# a-star-is31.net
KiCad netlist of a schematic drawn in EAGLE
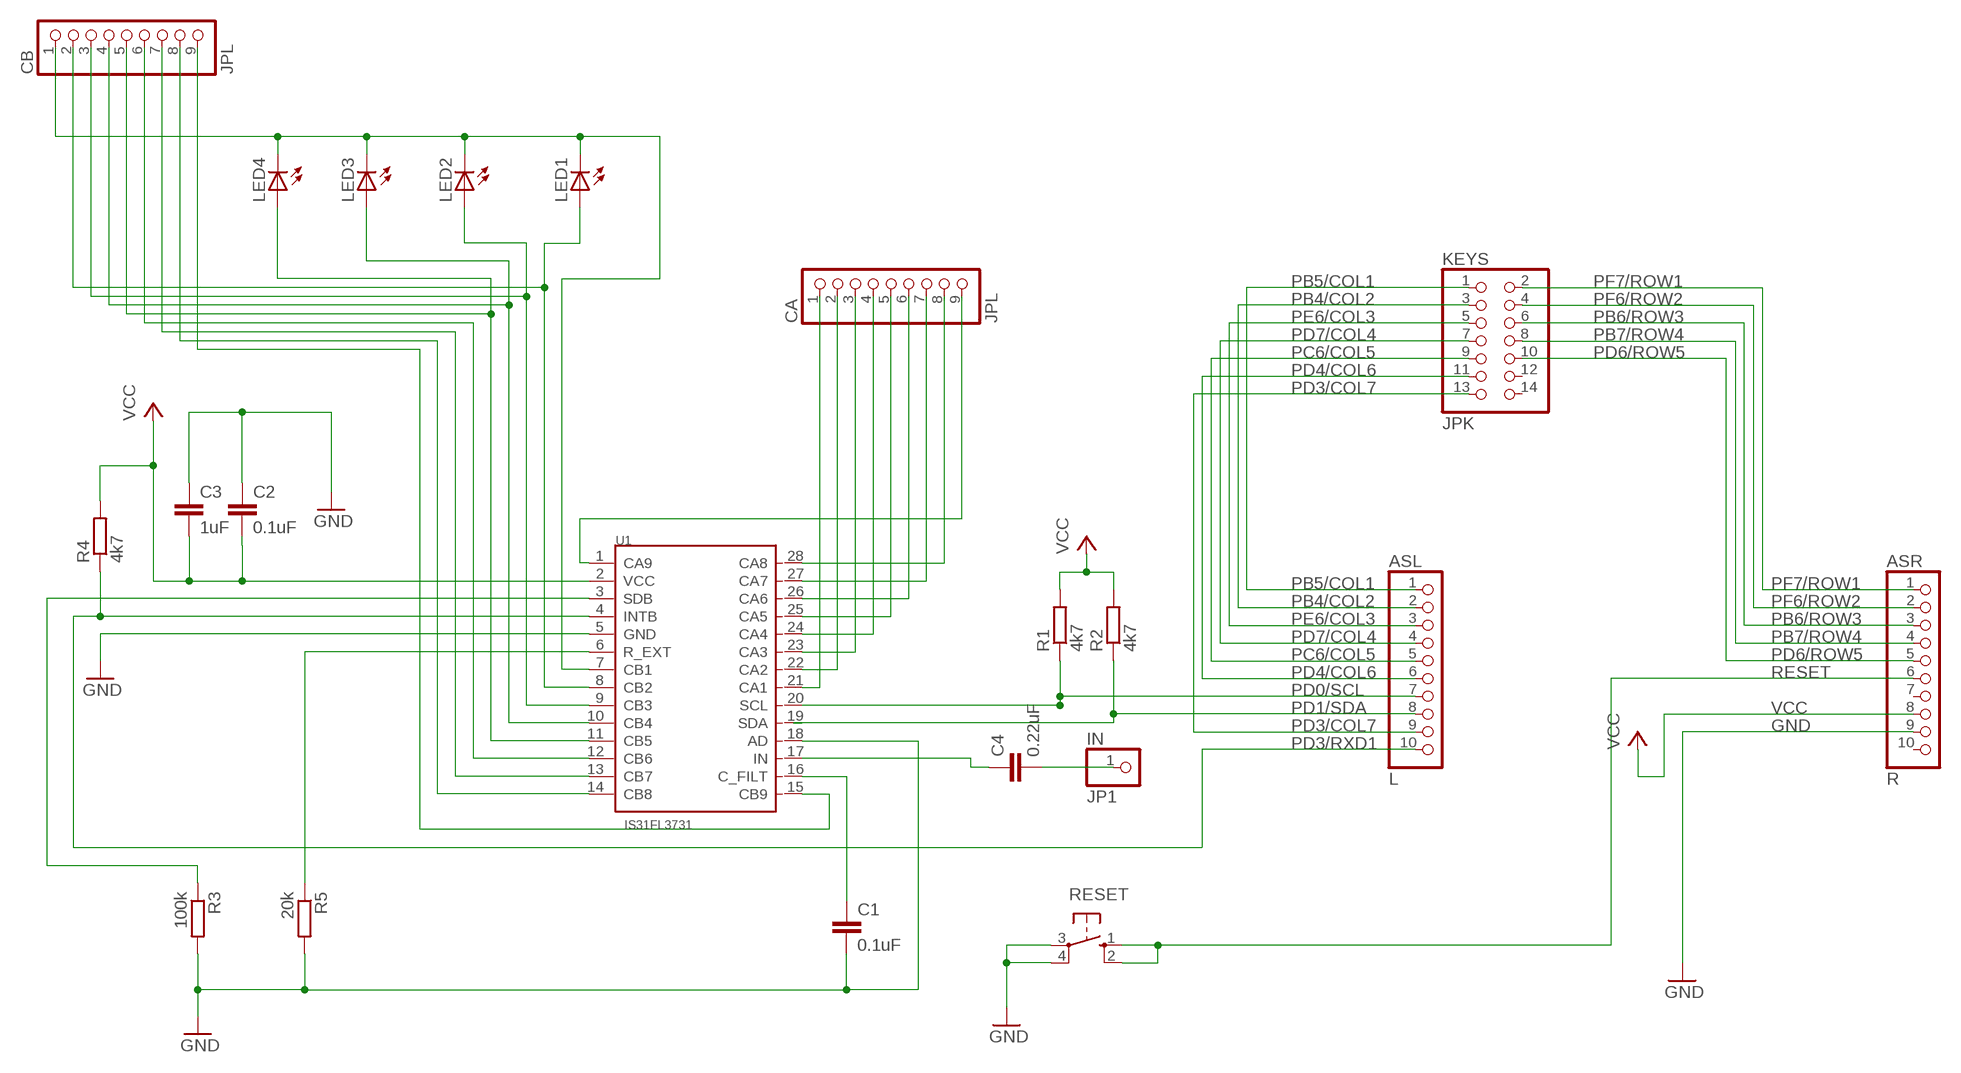
[diagram p0: schematic, sheet 1]

(export (version "E")
  (design (tool "Eeschema 10.0.6"))
  (components
    (comp (ref "ASL")
      (value "L")
      (footprint "eagle-import:1X10")
      (libsource (lib "eagle-import") (part "PINHD-1X10"))
    )
    (comp (ref "ASR")
      (value "R")
      (footprint "eagle-import:1X10")
      (libsource (lib "eagle-import") (part "PINHD-1X10"))
    )
    (comp (ref "C1")
      (value "0.1uF")
      (footprint "eagle-import:C025-025X050")
      (libsource (lib "eagle-import") (part "C-EU025-025X050"))
    )
    (comp (ref "C2")
      (value "0.1uF")
      (footprint "eagle-import:C025-025X050")
      (libsource (lib "eagle-import") (part "C-EU025-025X050"))
    )
    (comp (ref "C3")
      (value "1uF")
      (footprint "eagle-import:C025-025X050")
      (libsource (lib "eagle-import") (part "C-EU025-025X050"))
    )
    (comp (ref "C4")
      (value "0.22uF")
      (footprint "eagle-import:C025-025X050")
      (libsource (lib "eagle-import") (part "C-EU025-025X050"))
    )
    (comp (ref "CA")
      (value "JPL")
      (footprint "eagle-import:1X09")
      (libsource (lib "eagle-import") (part "PINHD-1X9"))
    )
    (comp (ref "CB")
      (value "JPL")
      (footprint "eagle-import:1X09")
      (libsource (lib "eagle-import") (part "PINHD-1X9"))
    )
    (comp (ref "IN")
      (value "JP1")
      (footprint "eagle-import:1X01")
      (libsource (lib "eagle-import") (part "PINHD-1X1"))
    )
    (comp (ref "KEYS")
      (value "JPK")
      (footprint "eagle-import:2X07")
      (libsource (lib "eagle-import") (part "PINHD-2X7"))
    )
    (comp (ref "LED1")
      (value "LED3MM")
      (footprint "eagle-import:LED3MM")
      (libsource (lib "eagle-import") (part "LED3MM"))
    )
    (comp (ref "LED2")
      (value "LED3MM")
      (footprint "eagle-import:LED3MM")
      (libsource (lib "eagle-import") (part "LED3MM"))
    )
    (comp (ref "LED3")
      (value "LED3MM")
      (footprint "eagle-import:LED3MM")
      (libsource (lib "eagle-import") (part "LED3MM"))
    )
    (comp (ref "LED4")
      (value "LED3MM")
      (footprint "eagle-import:LED3MM")
      (libsource (lib "eagle-import") (part "LED3MM"))
    )
    (comp (ref "R1")
      (value "4k7")
      (footprint "eagle-import:0207_10")
      (libsource (lib "eagle-import") (part "R-EU_0207/10"))
    )
    (comp (ref "R2")
      (value "4k7")
      (footprint "eagle-import:0207_10")
      (libsource (lib "eagle-import") (part "R-EU_0207/10"))
    )
    (comp (ref "R3")
      (value "100k")
      (footprint "eagle-import:0207_10")
      (libsource (lib "eagle-import") (part "R-EU_0207/10"))
    )
    (comp (ref "R4")
      (value "4k7")
      (footprint "eagle-import:0207_10")
      (libsource (lib "eagle-import") (part "R-EU_0207/10"))
    )
    (comp (ref "R5")
      (value "20k")
      (footprint "eagle-import:0207_10")
      (libsource (lib "eagle-import") (part "R-EU_0207/10"))
    )
    (comp (ref "RESET")
      (value "10-XX")
      (footprint "eagle-import:B3F-10XX")
      (fields (field (name "MPN") "B3F-1000"))
      (libsource (lib "eagle-import") (part "10-XX"))
    )
    (comp (ref "U1")
      (value "IS31FL3731")
      (footprint "eagle-import:SSOP28-0.65-10.2X5.2MM")
      (fields (field (name "MPN") "WM8731SEDS/V"))
      (libsource (lib "eagle-import") (part "IS31FL3731(SSOP28)"))
    )
  )
  (nets
    (net (code "1") (name "/PB4{slash}COL2") (class "Default")
      (node (ref "ASL") (pin "2") (pinfunction "2_2") (pintype "passive"))
      (node (ref "KEYS") (pin "3") (pinfunction "3_3") (pintype "passive"))
    )
    (net (code "2") (name "/PB5{slash}COL1") (class "Default")
      (node (ref "ASL") (pin "1") (pinfunction "1_1") (pintype "passive"))
      (node (ref "KEYS") (pin "1") (pinfunction "1_1") (pintype "passive"))
    )
    (net (code "3") (name "/PB6{slash}ROW3") (class "Default")
      (node (ref "ASR") (pin "3") (pinfunction "3_3") (pintype "passive"))
      (node (ref "KEYS") (pin "6") (pinfunction "6_6") (pintype "passive"))
    )
    (net (code "4") (name "/PB7{slash}ROW4") (class "Default")
      (node (ref "ASR") (pin "4") (pinfunction "4_4") (pintype "passive"))
      (node (ref "KEYS") (pin "8") (pinfunction "8_8") (pintype "passive"))
    )
    (net (code "5") (name "/PC6{slash}COL5") (class "Default")
      (node (ref "ASL") (pin "5") (pinfunction "5_5") (pintype "passive"))
      (node (ref "KEYS") (pin "9") (pinfunction "9_9") (pintype "passive"))
    )
    (net (code "6") (name "/PD0{slash}SCL") (class "Default")
      (node (ref "ASL") (pin "7") (pinfunction "7_7") (pintype "passive"))
      (node (ref "R1") (pin "1") (pinfunction "1_1") (pintype "passive"))
      (node (ref "U1") (pin "20") (pinfunction "SCL_20") (pintype "bidirectional"))
    )
    (net (code "7") (name "/PD1{slash}SDA") (class "Default")
      (node (ref "ASL") (pin "8") (pinfunction "8_8") (pintype "passive"))
      (node (ref "R2") (pin "1") (pinfunction "1_1") (pintype "passive"))
      (node (ref "U1") (pin "19") (pinfunction "SDA_19") (pintype "bidirectional"))
    )
    (net (code "8") (name "/PD3{slash}COL7") (class "Default")
      (node (ref "ASL") (pin "9") (pinfunction "9_9") (pintype "passive"))
      (node (ref "KEYS") (pin "13") (pinfunction "13_13") (pintype "passive"))
    )
    (net (code "9") (name "/PD3{slash}RXD1") (class "Default")
      (node (ref "ASL") (pin "10") (pinfunction "10_10") (pintype "passive"))
      (node (ref "R4") (pin "1") (pinfunction "1_1") (pintype "passive"))
      (node (ref "U1") (pin "4") (pinfunction "INTB_4") (pintype "bidirectional"))
    )
    (net (code "10") (name "/PD4{slash}COL6") (class "Default")
      (node (ref "ASL") (pin "6") (pinfunction "6_6") (pintype "passive"))
      (node (ref "KEYS") (pin "11") (pinfunction "11_11") (pintype "passive"))
    )
    (net (code "11") (name "/PD6{slash}ROW5") (class "Default")
      (node (ref "ASR") (pin "5") (pinfunction "5_5") (pintype "passive"))
      (node (ref "KEYS") (pin "10") (pinfunction "10_10") (pintype "passive"))
    )
    (net (code "12") (name "/PD7{slash}COL4") (class "Default")
      (node (ref "ASL") (pin "4") (pinfunction "4_4") (pintype "passive"))
      (node (ref "KEYS") (pin "7") (pinfunction "7_7") (pintype "passive"))
    )
    (net (code "13") (name "/PE6{slash}COL3") (class "Default")
      (node (ref "ASL") (pin "3") (pinfunction "3_3") (pintype "passive"))
      (node (ref "KEYS") (pin "5") (pinfunction "5_5") (pintype "passive"))
    )
    (net (code "14") (name "/PF6{slash}ROW2") (class "Default")
      (node (ref "ASR") (pin "2") (pinfunction "2_2") (pintype "passive"))
      (node (ref "KEYS") (pin "4") (pinfunction "4_4") (pintype "passive"))
    )
    (net (code "15") (name "/PF7{slash}ROW1") (class "Default")
      (node (ref "ASR") (pin "1") (pinfunction "1_1") (pintype "passive"))
      (node (ref "KEYS") (pin "2") (pinfunction "2_2") (pintype "passive"))
    )
    (net (code "16") (name "/RESET") (class "Default")
      (node (ref "ASR") (pin "6") (pinfunction "6_6") (pintype "passive"))
      (node (ref "RESET") (pin "1") (pinfunction "S_1") (pintype "passive"))
      (node (ref "RESET") (pin "2") (pinfunction "S1_2") (pintype "passive"))
    )
    (net (code "17") (name "GND") (class "Default")
      (node (ref "ASR") (pin "9") (pinfunction "9_9") (pintype "passive"))
      (node (ref "C1") (pin "2") (pinfunction "2_2") (pintype "passive"))
      (node (ref "C2") (pin "1") (pinfunction "1_1") (pintype "passive"))
      (node (ref "C3") (pin "1") (pinfunction "1_1") (pintype "passive"))
      (node (ref "R3") (pin "2") (pinfunction "2_2") (pintype "passive"))
      (node (ref "R5") (pin "2") (pinfunction "2_2") (pintype "passive"))
      (node (ref "RESET") (pin "3") (pinfunction "P_3") (pintype "passive"))
      (node (ref "RESET") (pin "4") (pinfunction "P1_4") (pintype "passive"))
      (node (ref "U1") (pin "18") (pinfunction "AD_18") (pintype "bidirectional"))
      (node (ref "U1") (pin "5") (pinfunction "GND_5") (pintype "bidirectional"))
    )
    (net (code "18") (name "Net-(C4-Pad2)") (class "Default")
      (node (ref "C4") (pin "2") (pinfunction "2_2") (pintype "passive"))
      (node (ref "IN") (pin "1") (pinfunction "1_1") (pintype "passive"))
    )
    (net (code "19") (name "Net-(LED1-C)") (class "Default")
      (node (ref "CB") (pin "1") (pinfunction "1_1") (pintype "passive"))
      (node (ref "LED1") (pin "K") (pinfunction "C_K") (pintype "passive"))
      (node (ref "LED2") (pin "K") (pinfunction "C_K") (pintype "passive"))
      (node (ref "LED3") (pin "K") (pinfunction "C_K") (pintype "passive"))
      (node (ref "LED4") (pin "K") (pinfunction "C_K") (pintype "passive"))
      (node (ref "U1") (pin "7") (pinfunction "CB1_7") (pintype "bidirectional"))
    )
    (net (code "20") (name "Net-(U1-CA1)") (class "Default")
      (node (ref "CA") (pin "1") (pinfunction "1_1") (pintype "passive"))
      (node (ref "U1") (pin "21") (pinfunction "CA1_21") (pintype "bidirectional"))
    )
    (net (code "21") (name "Net-(U1-CA2)") (class "Default")
      (node (ref "CA") (pin "2") (pinfunction "2_2") (pintype "passive"))
      (node (ref "U1") (pin "22") (pinfunction "CA2_22") (pintype "bidirectional"))
    )
    (net (code "22") (name "Net-(U1-CA3)") (class "Default")
      (node (ref "CA") (pin "3") (pinfunction "3_3") (pintype "passive"))
      (node (ref "U1") (pin "23") (pinfunction "CA3_23") (pintype "bidirectional"))
    )
    (net (code "23") (name "Net-(U1-CA4)") (class "Default")
      (node (ref "CA") (pin "4") (pinfunction "4_4") (pintype "passive"))
      (node (ref "U1") (pin "24") (pinfunction "CA4_24") (pintype "bidirectional"))
    )
    (net (code "24") (name "Net-(U1-CA5)") (class "Default")
      (node (ref "CA") (pin "5") (pinfunction "5_5") (pintype "passive"))
      (node (ref "U1") (pin "25") (pinfunction "CA5_25") (pintype "bidirectional"))
    )
    (net (code "25") (name "Net-(U1-CA6)") (class "Default")
      (node (ref "CA") (pin "6") (pinfunction "6_6") (pintype "passive"))
      (node (ref "U1") (pin "26") (pinfunction "CA6_26") (pintype "bidirectional"))
    )
    (net (code "26") (name "Net-(U1-CA7)") (class "Default")
      (node (ref "CA") (pin "7") (pinfunction "7_7") (pintype "passive"))
      (node (ref "U1") (pin "27") (pinfunction "CA7_27") (pintype "power_in"))
    )
    (net (code "27") (name "Net-(U1-CA8)") (class "Default")
      (node (ref "CA") (pin "8") (pinfunction "8_8") (pintype "passive"))
      (node (ref "U1") (pin "28") (pinfunction "CA8_28") (pintype "power_in"))
    )
    (net (code "28") (name "Net-(U1-CA9)") (class "Default")
      (node (ref "CA") (pin "9") (pinfunction "9_9") (pintype "passive"))
      (node (ref "U1") (pin "1") (pinfunction "CA9_1") (pintype "power_in"))
    )
    (net (code "29") (name "Net-(U1-CB2)") (class "Default")
      (node (ref "CB") (pin "2") (pinfunction "2_2") (pintype "passive"))
      (node (ref "LED1") (pin "A") (pinfunction "A_A") (pintype "passive"))
      (node (ref "U1") (pin "8") (pinfunction "CB2_8") (pintype "power_in"))
    )
    (net (code "30") (name "Net-(U1-CB3)") (class "Default")
      (node (ref "CB") (pin "3") (pinfunction "3_3") (pintype "passive"))
      (node (ref "LED2") (pin "A") (pinfunction "A_A") (pintype "passive"))
      (node (ref "U1") (pin "9") (pinfunction "CB3_9") (pintype "bidirectional"))
    )
    (net (code "31") (name "Net-(U1-CB4)") (class "Default")
      (node (ref "CB") (pin "4") (pinfunction "4_4") (pintype "passive"))
      (node (ref "LED3") (pin "A") (pinfunction "A_A") (pintype "passive"))
      (node (ref "U1") (pin "10") (pinfunction "CB4_10") (pintype "bidirectional"))
    )
    (net (code "32") (name "Net-(U1-CB5)") (class "Default")
      (node (ref "CB") (pin "5") (pinfunction "5_5") (pintype "passive"))
      (node (ref "LED4") (pin "A") (pinfunction "A_A") (pintype "passive"))
      (node (ref "U1") (pin "11") (pinfunction "CB5_11") (pintype "bidirectional"))
    )
    (net (code "33") (name "Net-(U1-CB6)") (class "Default")
      (node (ref "CB") (pin "6") (pinfunction "6_6") (pintype "passive"))
      (node (ref "U1") (pin "12") (pinfunction "CB6_12") (pintype "bidirectional"))
    )
    (net (code "34") (name "Net-(U1-CB7)") (class "Default")
      (node (ref "CB") (pin "7") (pinfunction "7_7") (pintype "passive"))
      (node (ref "U1") (pin "13") (pinfunction "CB7_13") (pintype "bidirectional"))
    )
    (net (code "35") (name "Net-(U1-CB8)") (class "Default")
      (node (ref "CB") (pin "8") (pinfunction "8_8") (pintype "passive"))
      (node (ref "U1") (pin "14") (pinfunction "CB8_14") (pintype "power_in"))
    )
    (net (code "36") (name "Net-(U1-CB9)") (class "Default")
      (node (ref "CB") (pin "9") (pinfunction "9_9") (pintype "passive"))
      (node (ref "U1") (pin "15") (pinfunction "CB9_15") (pintype "power_in"))
    )
    (net (code "37") (name "Net-(U1-C_FILT)") (class "Default")
      (node (ref "C1") (pin "1") (pinfunction "1_1") (pintype "passive"))
      (node (ref "U1") (pin "16") (pinfunction "C_FILT_16") (pintype "bidirectional"))
    )
    (net (code "38") (name "Net-(U1-IN)") (class "Default")
      (node (ref "C4") (pin "1") (pinfunction "1_1") (pintype "passive"))
      (node (ref "U1") (pin "17") (pinfunction "IN_17") (pintype "bidirectional"))
    )
    (net (code "39") (name "Net-(U1-R_EXT)") (class "Default")
      (node (ref "R5") (pin "1") (pinfunction "1_1") (pintype "passive"))
      (node (ref "U1") (pin "6") (pinfunction "R_EXT_6") (pintype "bidirectional"))
    )
    (net (code "40") (name "Net-(U1-SDB)") (class "Default")
      (node (ref "R3") (pin "1") (pinfunction "1_1") (pintype "passive"))
      (node (ref "U1") (pin "3") (pinfunction "SDB_3") (pintype "bidirectional"))
    )
    (net (code "41") (name "VCC") (class "Default")
      (node (ref "ASR") (pin "8") (pinfunction "8_8") (pintype "passive"))
      (node (ref "C2") (pin "2") (pinfunction "2_2") (pintype "passive"))
      (node (ref "C3") (pin "2") (pinfunction "2_2") (pintype "passive"))
      (node (ref "R1") (pin "2") (pinfunction "2_2") (pintype "passive"))
      (node (ref "R2") (pin "2") (pinfunction "2_2") (pintype "passive"))
      (node (ref "R4") (pin "2") (pinfunction "2_2") (pintype "passive"))
      (node (ref "U1") (pin "2") (pinfunction "VCC_2") (pintype "bidirectional"))
    )
    (net (code "42") (name "unconnected-(ASR-Pad7)") (class "Default")
      (node (ref "ASR") (pin "7") (pinfunction "7_7") (pintype "passive"))
    )
    (net (code "43") (name "unconnected-(ASR-Pad10)") (class "Default")
      (node (ref "ASR") (pin "10") (pinfunction "10_10") (pintype "passive"))
    )
    (net (code "44") (name "unconnected-(KEYS-Pad12)") (class "Default")
      (node (ref "KEYS") (pin "12") (pinfunction "12_12") (pintype "passive"))
    )
    (net (code "45") (name "unconnected-(KEYS-Pad14)") (class "Default")
      (node (ref "KEYS") (pin "14") (pinfunction "14_14") (pintype "passive"))
    )
  )
)
